# KDAC.net
KiCad netlist of a schematic drawn in EAGLE
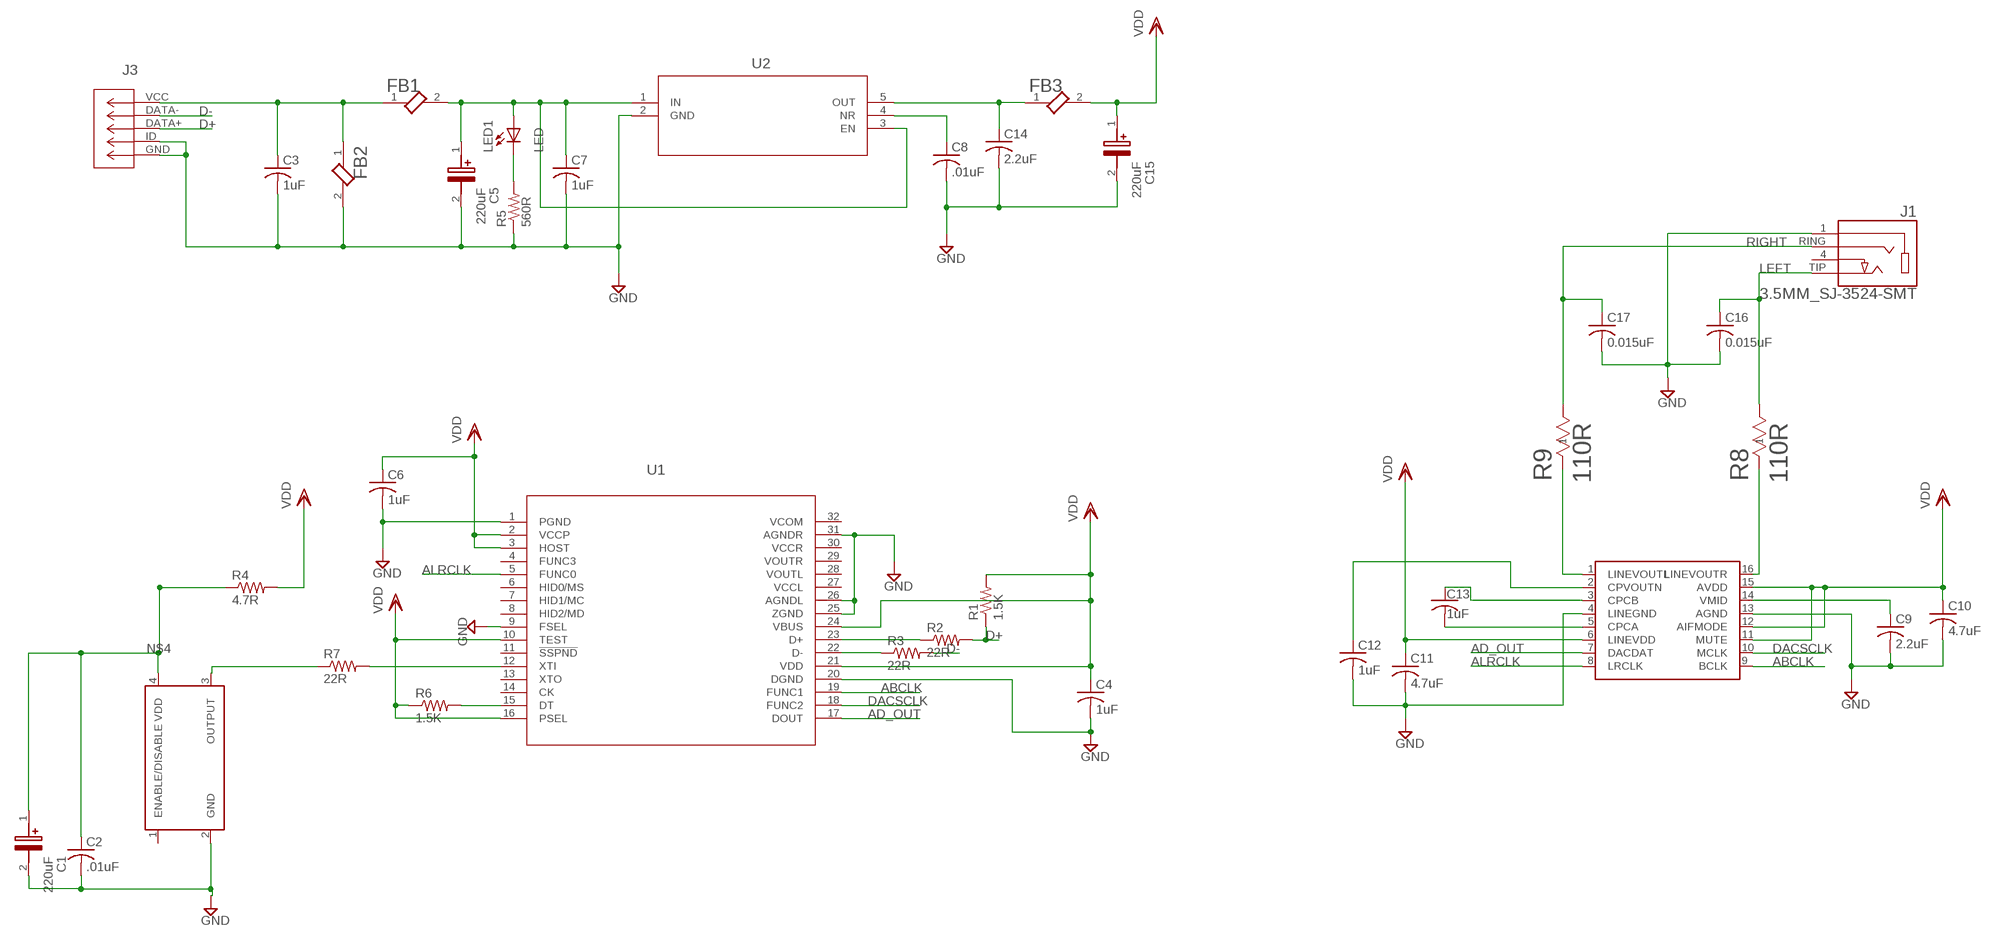
[diagram p0: schematic, sheet 1]

(export (version "E")
  (design (tool "Eeschema 10.0.6"))
  (components
    (comp (ref "C1")
      (value "220uF")
      (footprint "eagle-import:CAPAE830X1050N")
      (fields
        (field (name "ARROW_PART_NUMBER") "EEE-1VA221UP")
        (field (name "MOUSER_PART_NUMBER") "667-EEE-1VA221UP")
      )
      (libsource (lib "eagle-import") (part "EEE-1VA221UP"))
    )
    (comp (ref "C2")
      (value ".01uF")
      (footprint "eagle-import:C0805")
      (libsource (lib "eagle-import") (part "C-USC0805"))
    )
    (comp (ref "C3")
      (value "1uF")
      (footprint "eagle-import:C0805")
      (libsource (lib "eagle-import") (part "C-USC0805"))
    )
    (comp (ref "C4")
      (value "1uF")
      (footprint "eagle-import:C0805")
      (libsource (lib "eagle-import") (part "C-USC0805"))
    )
    (comp (ref "C5")
      (value "220uF")
      (footprint "eagle-import:CAPAE830X1050N")
      (fields
        (field (name "ARROW_PART_NUMBER") "EEE-1VA221UP")
        (field (name "MOUSER_PART_NUMBER") "667-EEE-1VA221UP")
      )
      (libsource (lib "eagle-import") (part "EEE-1VA221UP"))
    )
    (comp (ref "C6")
      (value "1uF")
      (footprint "eagle-import:C0805")
      (libsource (lib "eagle-import") (part "C-USC0805"))
    )
    (comp (ref "C7")
      (value "1uF")
      (footprint "eagle-import:C0805")
      (libsource (lib "eagle-import") (part "C-USC0805"))
    )
    (comp (ref "C8")
      (value ".01uF")
      (footprint "eagle-import:C0805")
      (libsource (lib "eagle-import") (part "C-USC0805"))
    )
    (comp (ref "C9")
      (value "2.2uF")
      (footprint "eagle-import:C0805")
      (libsource (lib "eagle-import") (part "C-USC0805"))
    )
    (comp (ref "C10")
      (value "4.7uF")
      (footprint "eagle-import:C0805")
      (libsource (lib "eagle-import") (part "C-USC0805"))
    )
    (comp (ref "C11")
      (value "4.7uF")
      (footprint "eagle-import:C0805")
      (libsource (lib "eagle-import") (part "C-USC0805"))
    )
    (comp (ref "C12")
      (value "1uF")
      (footprint "eagle-import:C0805")
      (libsource (lib "eagle-import") (part "C-USC0805"))
    )
    (comp (ref "C13")
      (value "1uF")
      (footprint "eagle-import:C0805")
      (libsource (lib "eagle-import") (part "C-USC0805"))
    )
    (comp (ref "C14")
      (value "2.2uF")
      (footprint "eagle-import:C0805")
      (libsource (lib "eagle-import") (part "C-USC0805"))
    )
    (comp (ref "C15")
      (value "220uF")
      (footprint "eagle-import:CAPAE830X1050N")
      (fields
        (field (name "ARROW_PART_NUMBER") "EEE-1VA221UP")
        (field (name "MOUSER_PART_NUMBER") "667-EEE-1VA221UP")
      )
      (libsource (lib "eagle-import") (part "EEE-1VA221UP"))
    )
    (comp (ref "C16")
      (value "0.015uF")
      (footprint "eagle-import:C050-075X075")
      (libsource (lib "eagle-import") (part "C-US050-075X075"))
    )
    (comp (ref "C17")
      (value "0.015uF")
      (footprint "eagle-import:C050-075X075")
      (libsource (lib "eagle-import") (part "C-US050-075X075"))
    )
    (comp (ref "FB1")
      (value "L_MURATA_BLM31PG601SN1LMURATA_BLM31PG601SN1L_0_2")
      (footprint "eagle-import:MURATA_BLM31PG601SN1L_2")
      (fields
        (field (name "3DS_PART_NUMBER") "310-00005")
        (field (name "DIGIKEY_PART_NUMBER") "490-1057-1-ND")
        (field (name "MF") "Murata")
      )
      (libsource (lib "eagle-import") (part "L_MURATA_BLM31PG601SN1LMURATA_BLM31PG601SN1L_0_2"))
    )
    (comp (ref "FB2")
      (value "L_MURATA_BLM31PG601SN1LMURATA_BLM31PG601SN1L_0_2")
      (footprint "eagle-import:MURATA_BLM31PG601SN1L_2")
      (fields
        (field (name "3DS_PART_NUMBER") "310-00005")
        (field (name "DIGIKEY_PART_NUMBER") "490-1057-1-ND")
        (field (name "MF") "Murata")
      )
      (libsource (lib "eagle-import") (part "L_MURATA_BLM31PG601SN1LMURATA_BLM31PG601SN1L_0_2"))
    )
    (comp (ref "FB3")
      (value "L_MURATA_BLM31PG601SN1LMURATA_BLM31PG601SN1L_0_2")
      (footprint "eagle-import:MURATA_BLM31PG601SN1L_2")
      (fields
        (field (name "3DS_PART_NUMBER") "310-00005")
        (field (name "DIGIKEY_PART_NUMBER") "490-1057-1-ND")
        (field (name "MF") "Murata")
      )
      (libsource (lib "eagle-import") (part "L_MURATA_BLM31PG601SN1LMURATA_BLM31PG601SN1L_0_2"))
    )
    (comp (ref "J1")
      (value "3.5MM_SJ-3524-SMT")
      (footprint "eagle-import:CUI_SJ-3524-SMT")
      (fields (field (name "MF") "CUI Inc"))
      (libsource (lib "eagle-import") (part "3.5MM_SJ-3524-SMT"))
    )
    (comp (ref "J3")
      (value "USB-MICRO-B_10118192-0002LF")
      (footprint "eagle-import:CONN_10118192-0002LF_AMP")
      (fields
        (field (name "MANUFACTURER_PART_NUMBER") "10118192-0002LF")
        (field (name "COPYRIGHT") "Copyright (C) 2018 Accelerated Designs. All rights reserved")
      )
      (libsource (lib "eagle-import") (part "USB-MICRO-B_10118192-0002LF"))
    )
    (comp (ref "LED1")
      (value "LED")
      (footprint "eagle-import:LED_2.54MM_0.5MM")
      (libsource (lib "eagle-import") (part "LED"))
    )
    (comp (ref "R1")
      (value "1.5K")
      (footprint "eagle-import:R1206")
      (libsource (lib "eagle-import") (part "R-US_R1206"))
    )
    (comp (ref "R2")
      (value "22R")
      (footprint "eagle-import:R1206")
      (libsource (lib "eagle-import") (part "R-US_R1206"))
    )
    (comp (ref "R3")
      (value "22R")
      (footprint "eagle-import:R1206")
      (libsource (lib "eagle-import") (part "R-US_R1206"))
    )
    (comp (ref "R4")
      (value "4.7R")
      (footprint "eagle-import:R1206")
      (libsource (lib "eagle-import") (part "R-US_R1206"))
    )
    (comp (ref "R5")
      (value "560R")
      (footprint "eagle-import:R1206")
      (libsource (lib "eagle-import") (part "R-US_R1206"))
    )
    (comp (ref "R6")
      (value "1.5K")
      (footprint "eagle-import:R1206")
      (libsource (lib "eagle-import") (part "R-US_R1206"))
    )
    (comp (ref "R7")
      (value "22R")
      (footprint "eagle-import:R1206")
      (libsource (lib "eagle-import") (part "R-US_R1206"))
    )
    (comp (ref "R8")
      (value "110R")
      (footprint "eagle-import:RES_CMF50")
      (fields (field (name "MANUFACTURER_PART_NUMBER") "CMF50110R00FHEB"))
      (libsource (lib "eagle-import") (part "R_CMF50110R00FHEB"))
    )
    (comp (ref "R9")
      (value "110R")
      (footprint "eagle-import:RES_CMF50")
      (fields (field (name "MANUFACTURER_PART_NUMBER") "CMF50110R00FHEB"))
      (libsource (lib "eagle-import") (part "R_CMF50110R00FHEB"))
    )
    (comp (ref "U1")
      (value "PCM2706CPJTRPJT32-M")
      (footprint "eagle-import:PJT32-M")
      (fields
        (field (name "MANUFACTURER") "Texas Instruments")
        (field (name "MANUFACTURER_PART_NUMBER") "PCM2706CPJTR")
      )
      (libsource (lib "eagle-import") (part "PCM2706CPJTRPJT32-M"))
    )
    (comp (ref "U2")
      (value "TPS79333DBVRDBV5_TEX-M")
      (footprint "eagle-import:DBV5_TEX-M")
      (fields
        (field (name "MANUFACTURER") "Texas Instruments")
        (field (name "MANUFACTURER_PART_NUMBER") "TPS79333DBVR")
      )
      (libsource (lib "eagle-import") (part "TPS79333DBVRDBV5_TEX-M"))
    )
    (comp (ref "U3")
      (value "WM8524ALT")
      (footprint "eagle-import:SOP65P640X110-16N")
      (libsource (lib "eagle-import") (part "WM8524ALT"))
    )
    (comp (ref "X1")
      (value "ASV-12MHZ")
      (footprint "eagle-import:ASV_12MHZ_4SMD-M")
      (libsource (lib "eagle-import") (part "ASV-12MHZ"))
    )
  )
  (nets
    (net (code "1") (name "/ABCLK") (class "Default")
      (node (ref "U1") (pin "19") (pinfunction "FUNC1_19") (pintype "bidirectional"))
      (node (ref "U3") (pin "9") (pinfunction "BCLK_9") (pintype "output"))
    )
    (net (code "2") (name "/AD_OUT") (class "Default")
      (node (ref "U1") (pin "17") (pinfunction "DOUT_17") (pintype "output"))
      (node (ref "U3") (pin "7") (pinfunction "DACDAT_7") (pintype "output"))
    )
    (net (code "3") (name "/ALRCLK") (class "Default")
      (node (ref "U1") (pin "5") (pinfunction "FUNC0_5") (pintype "bidirectional"))
      (node (ref "U3") (pin "8") (pinfunction "LRCLK_8") (pintype "output"))
    )
    (net (code "4") (name "/D+") (class "Default")
      (node (ref "J3") (pin "DATA+") (pinfunction "DATA+_DATA+") (pintype "passive"))
      (node (ref "R1") (pin "1") (pinfunction "1_1") (pintype "passive"))
      (node (ref "R2") (pin "2") (pinfunction "2_2") (pintype "passive"))
    )
    (net (code "5") (name "/D-") (class "Default")
      (node (ref "J3") (pin "DATA-") (pinfunction "DATA-_DATA-") (pintype "passive"))
      (node (ref "R3") (pin "2") (pinfunction "2_2") (pintype "passive"))
    )
    (net (code "6") (name "/DACSCLK") (class "Default")
      (node (ref "U1") (pin "18") (pinfunction "FUNC2_18") (pintype "bidirectional"))
      (node (ref "U3") (pin "10") (pinfunction "MCLK_10") (pintype "output"))
    )
    (net (code "7") (name "/LEFT") (class "Default")
      (node (ref "C16") (pin "1") (pinfunction "1_1") (pintype "passive"))
      (node (ref "J1") (pin "TIP") (pinfunction "2_TIP") (pintype "passive"))
      (node (ref "R8") (pin "2") (pinfunction "2_2") (pintype "passive"))
    )
    (net (code "8") (name "/N$4") (class "Default")
      (node (ref "C1") (pin "1") (pinfunction "+_1") (pintype "bidirectional"))
      (node (ref "C2") (pin "1") (pinfunction "1_1") (pintype "passive"))
      (node (ref "R4") (pin "1") (pinfunction "1_1") (pintype "passive"))
      (node (ref "X1") (pin "4") (pinfunction "VDD_4") (pintype "output"))
    )
    (net (code "9") (name "/RIGHT") (class "Default")
      (node (ref "C17") (pin "1") (pinfunction "1_1") (pintype "passive"))
      (node (ref "J1") (pin "RING") (pinfunction "3_RING") (pintype "passive"))
      (node (ref "R9") (pin "2") (pinfunction "2_2") (pintype "passive"))
    )
    (net (code "10") (name "/VCCL") (class "Default")
      (node (ref "U1") (pin "27") (pinfunction "VCCL_27") (pintype "power_in"))
    )
    (net (code "11") (name "/VCCR") (class "Default")
      (node (ref "U1") (pin "30") (pinfunction "VCCR_30") (pintype "power_in"))
    )
    (net (code "12") (name "/VCOM") (class "Default")
      (node (ref "U1") (pin "32") (pinfunction "VCOM_32") (pintype "power_in"))
    )
    (net (code "13") (name "GND") (class "Default")
      (node (ref "C1") (pin "2") (pinfunction "-_2") (pintype "bidirectional"))
      (node (ref "C10") (pin "2") (pinfunction "2_2") (pintype "passive"))
      (node (ref "C11") (pin "2") (pinfunction "2_2") (pintype "passive"))
      (node (ref "C12") (pin "2") (pinfunction "2_2") (pintype "passive"))
      (node (ref "C14") (pin "2") (pinfunction "2_2") (pintype "passive"))
      (node (ref "C15") (pin "2") (pinfunction "-_2") (pintype "bidirectional"))
      (node (ref "C16") (pin "2") (pinfunction "2_2") (pintype "passive"))
      (node (ref "C17") (pin "2") (pinfunction "2_2") (pintype "passive"))
      (node (ref "C2") (pin "2") (pinfunction "2_2") (pintype "passive"))
      (node (ref "C3") (pin "2") (pinfunction "2_2") (pintype "passive"))
      (node (ref "C4") (pin "2") (pinfunction "2_2") (pintype "passive"))
      (node (ref "C5") (pin "2") (pinfunction "-_2") (pintype "bidirectional"))
      (node (ref "C6") (pin "2") (pinfunction "2_2") (pintype "passive"))
      (node (ref "C7") (pin "2") (pinfunction "2_2") (pintype "passive"))
      (node (ref "C8") (pin "2") (pinfunction "2_2") (pintype "passive"))
      (node (ref "C9") (pin "2") (pinfunction "2_2") (pintype "passive"))
      (node (ref "FB2") (pin "2") (pinfunction "2_2") (pintype "passive"))
      (node (ref "J1") (pin "1") (pinfunction "1_1") (pintype "passive"))
      (node (ref "J3") (pin "GND") (pinfunction "GND_GND") (pintype "passive"))
      (node (ref "J3") (pin "ID") (pinfunction "ID_ID") (pintype "passive"))
      (node (ref "R5") (pin "1") (pinfunction "1_1") (pintype "passive"))
      (node (ref "U1") (pin "1") (pinfunction "PGND_1") (pintype "power_in"))
      (node (ref "U1") (pin "20") (pinfunction "DGND_20") (pintype "power_in"))
      (node (ref "U1") (pin "25") (pinfunction "ZGND_25") (pintype "power_in"))
      (node (ref "U1") (pin "26") (pinfunction "AGNDL_26") (pintype "power_in"))
      (node (ref "U1") (pin "31") (pinfunction "AGNDR_31") (pintype "power_in"))
      (node (ref "U1") (pin "9") (pinfunction "FSEL_9") (pintype "input"))
      (node (ref "U2") (pin "2") (pinfunction "GND_2") (pintype "power_in"))
      (node (ref "U3") (pin "13") (pinfunction "AGND_13") (pintype "output"))
      (node (ref "U3") (pin "4") (pinfunction "LINEGND_4") (pintype "output"))
      (node (ref "X1") (pin "2") (pinfunction "GND_2") (pintype "output"))
    )
    (net (code "14") (name "Net-(C3-Pad1)") (class "Default")
      (node (ref "C3") (pin "1") (pinfunction "1_1") (pintype "passive"))
      (node (ref "FB1") (pin "1") (pinfunction "1_1") (pintype "passive"))
      (node (ref "FB2") (pin "1") (pinfunction "1_1") (pintype "passive"))
      (node (ref "J3") (pin "VCC") (pinfunction "VCC_VCC") (pintype "passive"))
    )
    (net (code "15") (name "Net-(C5-+)") (class "Default")
      (node (ref "C5") (pin "1") (pinfunction "+_1") (pintype "bidirectional"))
      (node (ref "C7") (pin "1") (pinfunction "1_1") (pintype "passive"))
      (node (ref "FB1") (pin "2") (pinfunction "2_2") (pintype "passive"))
      (node (ref "LED1") (pin "ANODE") (pinfunction "+_ANODE") (pintype "passive"))
      (node (ref "U2") (pin "1") (pinfunction "IN_1") (pintype "input"))
      (node (ref "U2") (pin "3") (pinfunction "EN_3") (pintype "passive"))
    )
    (net (code "16") (name "Net-(LED1--)") (class "Default")
      (node (ref "LED1") (pin "CATHODE") (pinfunction "-_CATHODE") (pintype "passive"))
      (node (ref "R5") (pin "2") (pinfunction "2_2") (pintype "passive"))
    )
    (net (code "17") (name "Net-(U1-D+)") (class "Default")
      (node (ref "R2") (pin "1") (pinfunction "1_1") (pintype "passive"))
      (node (ref "U1") (pin "23") (pinfunction "D+_23") (pintype "bidirectional"))
    )
    (net (code "18") (name "Net-(U1-D-)") (class "Default")
      (node (ref "R3") (pin "1") (pinfunction "1_1") (pintype "passive"))
      (node (ref "U1") (pin "22") (pinfunction "D-_22") (pintype "bidirectional"))
    )
    (net (code "19") (name "Net-(U1-DT)") (class "Default")
      (node (ref "R6") (pin "2") (pinfunction "2_2") (pintype "passive"))
      (node (ref "U1") (pin "15") (pinfunction "DT_15") (pintype "bidirectional"))
    )
    (net (code "20") (name "Net-(U1-XTI)") (class "Default")
      (node (ref "R7") (pin "2") (pinfunction "2_2") (pintype "passive"))
      (node (ref "U1") (pin "12") (pinfunction "XTI_12") (pintype "input"))
    )
    (net (code "21") (name "Net-(U2-NR)") (class "Default")
      (node (ref "C8") (pin "1") (pinfunction "1_1") (pintype "passive"))
      (node (ref "U2") (pin "4") (pinfunction "NR_4") (pintype "passive"))
    )
    (net (code "22") (name "Net-(U2-OUT)") (class "Default")
      (node (ref "C14") (pin "1") (pinfunction "1_1") (pintype "passive"))
      (node (ref "FB3") (pin "1") (pinfunction "1_1") (pintype "passive"))
      (node (ref "U2") (pin "5") (pinfunction "OUT_5") (pintype "output"))
    )
    (net (code "23") (name "Net-(U3-CPCA)") (class "Default")
      (node (ref "C13") (pin "2") (pinfunction "2_2") (pintype "passive"))
      (node (ref "U3") (pin "5") (pinfunction "CPCA_5") (pintype "output"))
    )
    (net (code "24") (name "Net-(U3-CPCB)") (class "Default")
      (node (ref "C13") (pin "1") (pinfunction "1_1") (pintype "passive"))
      (node (ref "U3") (pin "3") (pinfunction "CPCB_3") (pintype "output"))
    )
    (net (code "25") (name "Net-(U3-CPVOUTN)") (class "Default")
      (node (ref "C12") (pin "1") (pinfunction "1_1") (pintype "passive"))
      (node (ref "U3") (pin "2") (pinfunction "CPVOUTN_2") (pintype "output"))
    )
    (net (code "26") (name "Net-(U3-LINEVOUTL)") (class "Default")
      (node (ref "R9") (pin "1") (pinfunction "1_1") (pintype "passive"))
      (node (ref "U3") (pin "1") (pinfunction "LINEVOUTL_1") (pintype "output"))
    )
    (net (code "27") (name "Net-(U3-LINEVOUTR)") (class "Default")
      (node (ref "R8") (pin "1") (pinfunction "1_1") (pintype "passive"))
      (node (ref "U3") (pin "16") (pinfunction "LINEVOUTR_16") (pintype "output"))
    )
    (net (code "28") (name "Net-(U3-VMID)") (class "Default")
      (node (ref "C9") (pin "1") (pinfunction "1_1") (pintype "passive"))
      (node (ref "U3") (pin "14") (pinfunction "VMID_14") (pintype "output"))
    )
    (net (code "29") (name "Net-(X1-OUTPUT)") (class "Default")
      (node (ref "R7") (pin "1") (pinfunction "1_1") (pintype "passive"))
      (node (ref "X1") (pin "3") (pinfunction "OUTPUT_3") (pintype "output"))
    )
    (net (code "30") (name "VDD") (class "Default")
      (node (ref "C10") (pin "1") (pinfunction "1_1") (pintype "passive"))
      (node (ref "C11") (pin "1") (pinfunction "1_1") (pintype "passive"))
      (node (ref "C15") (pin "1") (pinfunction "+_1") (pintype "bidirectional"))
      (node (ref "C4") (pin "1") (pinfunction "1_1") (pintype "passive"))
      (node (ref "C6") (pin "1") (pinfunction "1_1") (pintype "passive"))
      (node (ref "FB3") (pin "2") (pinfunction "2_2") (pintype "passive"))
      (node (ref "R1") (pin "2") (pinfunction "2_2") (pintype "passive"))
      (node (ref "R4") (pin "2") (pinfunction "2_2") (pintype "passive"))
      (node (ref "R6") (pin "1") (pinfunction "1_1") (pintype "passive"))
      (node (ref "U1") (pin "10") (pinfunction "TEST_10") (pintype "input"))
      (node (ref "U1") (pin "16") (pinfunction "PSEL_16") (pintype "input"))
      (node (ref "U1") (pin "2") (pinfunction "VCCP_2") (pintype "power_in"))
      (node (ref "U1") (pin "21") (pinfunction "VDD_21") (pintype "power_in"))
      (node (ref "U1") (pin "24") (pinfunction "VBUS_24") (pintype "power_in"))
      (node (ref "U1") (pin "3") (pinfunction "HOST_3") (pintype "input"))
      (node (ref "U3") (pin "11") (pinfunction "MUTE_11") (pintype "output"))
      (node (ref "U3") (pin "12") (pinfunction "AIFMODE_12") (pintype "output"))
      (node (ref "U3") (pin "15") (pinfunction "AVDD_15") (pintype "output"))
      (node (ref "U3") (pin "6") (pinfunction "LINEVDD_6") (pintype "output"))
    )
    (net (code "31") (name "unconnected-(J1-Pad4)") (class "Default")
      (node (ref "J1") (pin "4") (pinfunction "4_4") (pintype "passive"))
    )
    (net (code "32") (name "unconnected-(U1-CK-Pad14)") (class "Default")
      (node (ref "U1") (pin "14") (pinfunction "CK_14") (pintype "output"))
    )
    (net (code "33") (name "unconnected-(U1-FUNC3-Pad4)") (class "Default")
      (node (ref "U1") (pin "4") (pinfunction "FUNC3_4") (pintype "input"))
    )
    (net (code "34") (name "unconnected-(U1-HID0{slash}MS-Pad6)") (class "Default")
      (node (ref "U1") (pin "6") (pinfunction "HID0/MS_6") (pintype "input"))
    )
    (net (code "35") (name "unconnected-(U1-HID1{slash}MC-Pad7)") (class "Default")
      (node (ref "U1") (pin "7") (pinfunction "HID1/MC_7") (pintype "input"))
    )
    (net (code "36") (name "unconnected-(U1-HID2{slash}MD-Pad8)") (class "Default")
      (node (ref "U1") (pin "8") (pinfunction "HID2/MD_8") (pintype "input"))
    )
    (net (code "37") (name "unconnected-(U1-VOUTL-Pad28)") (class "Default")
      (node (ref "U1") (pin "28") (pinfunction "VOUTL_28") (pintype "output"))
    )
    (net (code "38") (name "unconnected-(U1-VOUTR-Pad29)") (class "Default")
      (node (ref "U1") (pin "29") (pinfunction "VOUTR_29") (pintype "output"))
    )
    (net (code "39") (name "unconnected-(U1-XTO-Pad13)") (class "Default")
      (node (ref "U1") (pin "13") (pinfunction "XTO_13") (pintype "output"))
    )
    (net (code "40") (name "unconnected-(U1-~{SSPND}-Pad11)") (class "Default")
      (node (ref "U1") (pin "11") (pinfunction "~{SSPND}_11") (pintype "output"))
    )
    (net (code "41") (name "unconnected-(X1-ENABLE{slash}DISABLE-Pad1)") (class "Default")
      (node (ref "X1") (pin "1") (pinfunction "ENABLE/DISABLE_1") (pintype "output"))
    )
  )
)
